# SCHEMATIC_RELAY_DIFFERENTIAL.net
KiCad netlist of a schematic drawn in EasyEDA
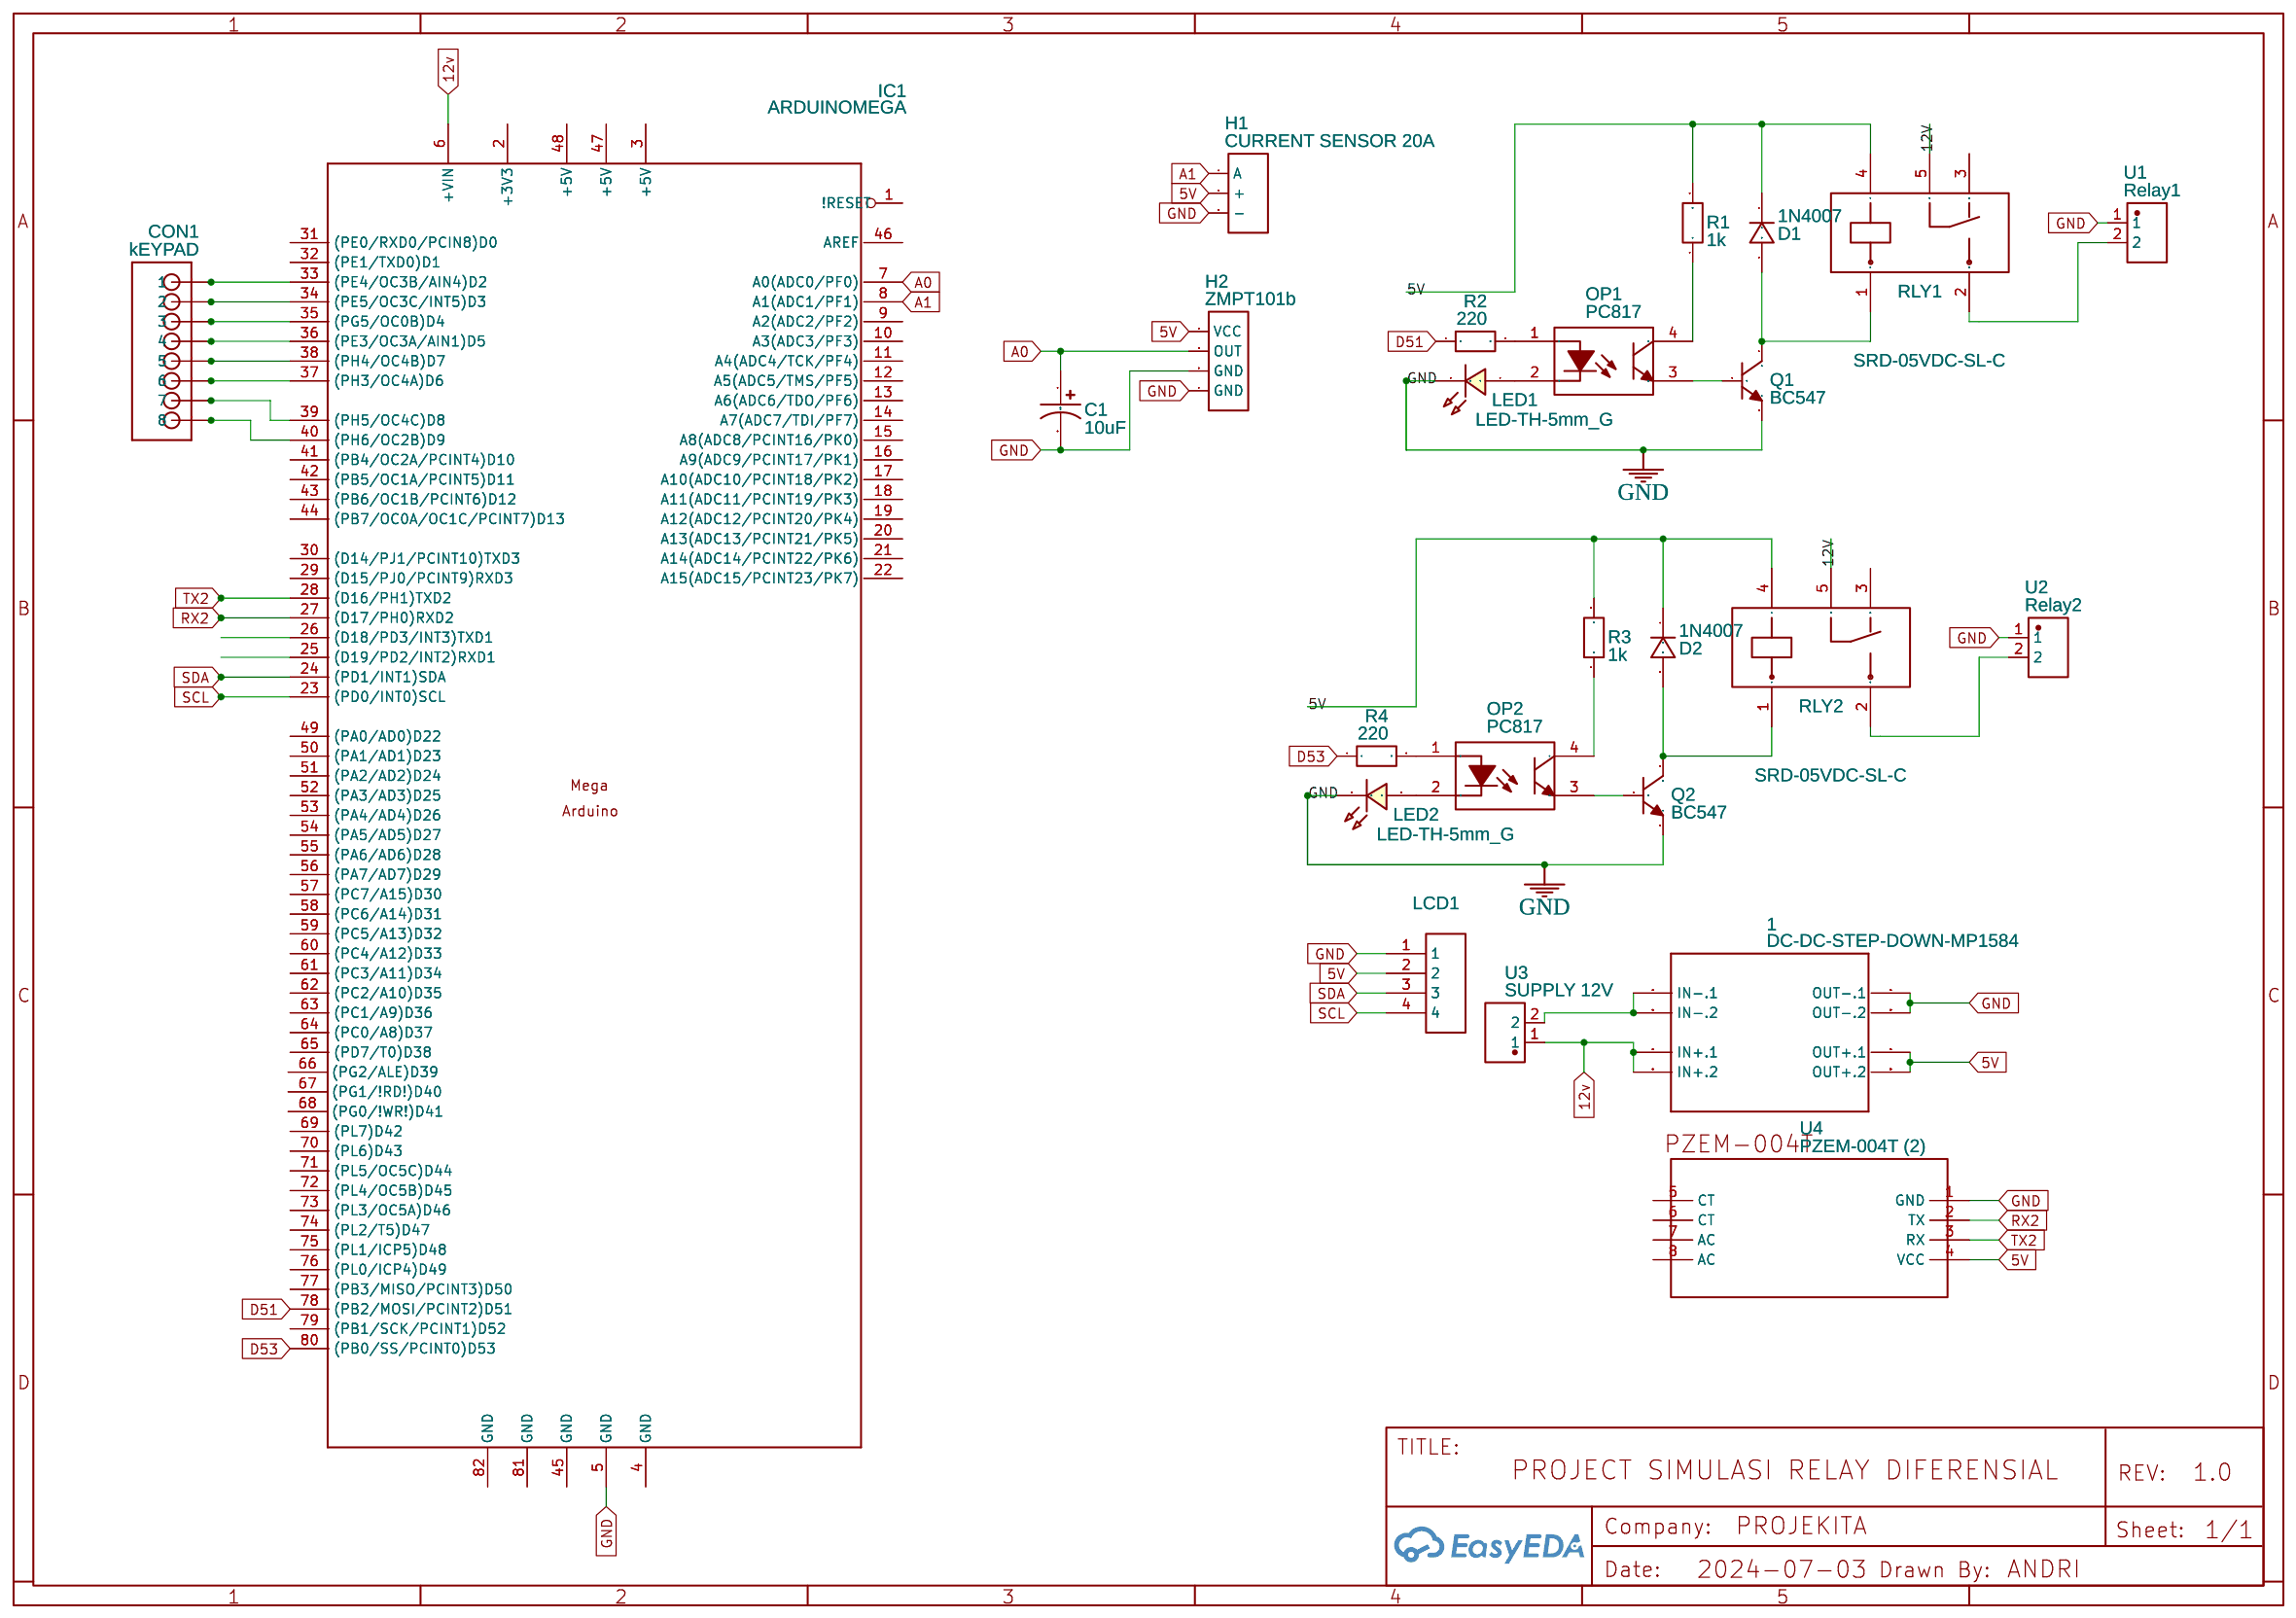
[diagram p0: schematic sheet]

(export (version "E")
  (design (tool "Eeschema 10.0.6"))
  (components
    (comp (ref "1") (value "DC-DC-STEP-DOWN-MP1584") (libsource (lib "") (part "DC-DC-STEP-DOWN-MP1584")))
    (comp (ref "C1") (value "10uF") (libsource (lib "") (part "CE_TH_D4.0×F1.5_US")))
    (comp (ref "CON1") (value "kEYPAD") (libsource (lib "") (part "JST XH2.54 8P")))
    (comp (ref "D1")
      (value "1N4007")
      (fields (field (name "Manufacturer") "SEMTECH"))
      (libsource (lib "") (part "1N4007"))
    )
    (comp (ref "D2")
      (value "1N4007")
      (fields (field (name "Manufacturer") "SEMTECH"))
      (libsource (lib "") (part "1N4007"))
    )
    (comp (ref "H1") (value "CURRENT SENSOR 20A") (libsource (lib "") (part "HDR-F-2.54_1x3")))
    (comp (ref "H2") (value "ZMPT101b") (libsource (lib "") (part "HDR-F-2.54_1x4")))
    (comp (ref "IC1") (value "ARDUINOMEGA") (libsource (lib "") (part "ARDUINOMEGA")))
    (comp (ref "LCD1") (value "NO") (libsource (lib "") (part "JST XH2.54 4 PIN")))
    (comp (ref "LED1")
      (value "LED-TH-5mm_G")
      (fields
        (field (name "Manufacturer Part") "333-2SYGD/S530-E2")
        (field (name "Manufacturer") "EVERLIGHT(台湾亿光)")
      )
      (libsource (lib "") (part "LED-TH-5mm_G"))
    )
    (comp (ref "LED2")
      (value "LED-TH-5mm_G")
      (fields
        (field (name "Manufacturer Part") "333-2SYGD/S530-E2")
        (field (name "Manufacturer") "EVERLIGHT(台湾亿光)")
      )
      (libsource (lib "") (part "LED-TH-5mm_G"))
    )
    (comp (ref "OP1") (value "PC817") (libsource (lib "") (part "PC817")))
    (comp (ref "OP2") (value "PC817") (libsource (lib "") (part "PC817")))
    (comp (ref "Q1")
      (value "BC547")
      (fields (field (name "Manufacturer") "CJ(江苏长电/长晶)"))
      (libsource (lib "") (part "BC547"))
    )
    (comp (ref "Q2")
      (value "BC547")
      (fields (field (name "Manufacturer") "CJ(江苏长电/长晶)"))
      (libsource (lib "") (part "BC547"))
    )
    (comp (ref "R1") (value "1k") (libsource (lib "") (part "R_AXIAL-0.4_EU")))
    (comp (ref "R2") (value "220") (libsource (lib "") (part "R_AXIAL-0.4_EU_1")))
    (comp (ref "R3") (value "1k") (libsource (lib "") (part "R_AXIAL-0.4_EU")))
    (comp (ref "R4") (value "220") (libsource (lib "") (part "R_AXIAL-0.4_EU_1")))
    (comp (ref "RLY1")
      (value "SRD-05VDC-SL-C")
      (fields (field (name "Manufacturer") "松乐"))
      (libsource (lib "") (part "SRD-05VDC-SL-C"))
    )
    (comp (ref "RLY2")
      (value "SRD-05VDC-SL-C")
      (fields (field (name "Manufacturer") "松乐"))
      (libsource (lib "") (part "SRD-05VDC-SL-C"))
    )
    (comp (ref "U1")
      (value "Relay1")
      (fields (field (name "Manufacturer Part") "KF25H-7.62-2P") (field (name "Manufacturer") "KEFA(科发)"))
      (libsource (lib "") (part "KF25H-7.62-2P_1"))
    )
    (comp (ref "U2")
      (value "Relay2")
      (fields (field (name "Manufacturer Part") "KF25H-7.62-2P") (field (name "Manufacturer") "KEFA(科发)"))
      (libsource (lib "") (part "KF25H-7.62-2P_1"))
    )
    (comp (ref "U3")
      (value "SUPPLY 12V")
      (fields (field (name "Manufacturer Part") "KF25H-7.62-2P") (field (name "Manufacturer") "KEFA(科发)"))
      (libsource (lib "") (part "KF25H-7.62-2P"))
    )
    (comp (ref "U4") (value "PZEM-004T (2)") (libsource (lib "") (part "PZEM-004T")))
  )
  (nets
    (net (code "1") (name "/12V") (class "Default")
      (node (ref "RLY1") (pin "5") (pinfunction "5_5") (pintype "input"))
      (node (ref "RLY2") (pin "5") (pinfunction "5_5") (pintype "input"))
    )
    (net (code "2") (name "5V") (class "Default")
      (node (ref "1") (pin "OUT+.1") (pinfunction "OUT+.1_OUT+.1") (pintype "bidirectional"))
      (node (ref "1") (pin "OUT+.2") (pinfunction "OUT+.2_OUT+.2") (pintype "bidirectional"))
      (node (ref "D1") (pin "1") (pinfunction "1_1") (pintype "unspecified"))
      (node (ref "D2") (pin "1") (pinfunction "1_1") (pintype "unspecified"))
      (node (ref "H1") (pin "2") (pinfunction "+_2") (pintype "input"))
      (node (ref "H2") (pin "1") (pinfunction "VCC_1") (pintype "unspecified"))
      (node (ref "LCD1") (pin "2") (pinfunction "2_2") (pintype "unspecified"))
      (node (ref "R1") (pin "2") (pinfunction "2_2") (pintype "unspecified"))
      (node (ref "R3") (pin "2") (pinfunction "2_2") (pintype "unspecified"))
      (node (ref "RLY1") (pin "4") (pinfunction "4_4") (pintype "input"))
      (node (ref "RLY2") (pin "4") (pinfunction "4_4") (pintype "input"))
      (node (ref "U4") (pin "4") (pinfunction "VCC_4") (pintype "unspecified"))
    )
    (net (code "3") (name "12v") (class "Default")
      (node (ref "1") (pin "IN+.1") (pinfunction "IN+.1_IN+.1") (pintype "bidirectional"))
      (node (ref "1") (pin "IN+.2") (pinfunction "IN+.2_IN+.2") (pintype "bidirectional"))
      (node (ref "IC1") (pin "6") (pinfunction "+VIN_6") (pintype "bidirectional"))
      (node (ref "U3") (pin "1") (pinfunction "1_1") (pintype "unspecified"))
    )
    (net (code "4") (name "A0") (class "Default")
      (node (ref "C1") (pin "1") (pinfunction "1_1") (pintype "unspecified"))
      (node (ref "H2") (pin "2") (pinfunction "OUT_2") (pintype "unspecified"))
      (node (ref "IC1") (pin "7") (pinfunction "A0(ADC0/PF0)_7") (pintype "bidirectional"))
    )
    (net (code "5") (name "A1") (class "Default")
      (node (ref "H1") (pin "1") (pinfunction "A_1") (pintype "input"))
      (node (ref "IC1") (pin "8") (pinfunction "A1(ADC1/PF1)_8") (pintype "bidirectional"))
    )
    (net (code "6") (name "D51") (class "Default")
      (node (ref "IC1") (pin "78") (pinfunction "(PB2/MOSI/PCINT2)D51_78") (pintype "bidirectional"))
      (node (ref "R2") (pin "1") (pinfunction "1_1") (pintype "unspecified"))
    )
    (net (code "7") (name "D53") (class "Default")
      (node (ref "IC1") (pin "80") (pinfunction "(PB0/SS/PCINT0)D53_80") (pintype "bidirectional"))
      (node (ref "R4") (pin "1") (pinfunction "1_1") (pintype "unspecified"))
    )
    (net (code "8") (name "GND") (class "Default")
      (node (ref "1") (pin "OUT-.1") (pinfunction "OUT-.1_OUT-.1") (pintype "bidirectional"))
      (node (ref "1") (pin "OUT-.2") (pinfunction "OUT-.2_OUT-.2") (pintype "bidirectional"))
      (node (ref "C1") (pin "2") (pinfunction "2_2") (pintype "unspecified"))
      (node (ref "H1") (pin "3") (pinfunction "-_3") (pintype "input"))
      (node (ref "H2") (pin "3") (pinfunction "GND_3") (pintype "unspecified"))
      (node (ref "H2") (pin "4") (pinfunction "GND_4") (pintype "unspecified"))
      (node (ref "IC1") (pin "5") (pinfunction "GND_5") (pintype "bidirectional"))
      (node (ref "LCD1") (pin "1") (pinfunction "1_1") (pintype "unspecified"))
      (node (ref "LED1") (pin "2") (pinfunction "2_2") (pintype "unspecified"))
      (node (ref "LED2") (pin "2") (pinfunction "2_2") (pintype "unspecified"))
      (node (ref "Q1") (pin "3") (pinfunction "E_3") (pintype "unspecified"))
      (node (ref "Q2") (pin "3") (pinfunction "E_3") (pintype "unspecified"))
      (node (ref "U1") (pin "1") (pinfunction "1_1") (pintype "unspecified"))
      (node (ref "U2") (pin "1") (pinfunction "1_1") (pintype "unspecified"))
      (node (ref "U4") (pin "1") (pinfunction "GND_1") (pintype "unspecified"))
    )
    (net (code "9") (name "Net-(1-PadIN-.1)") (class "Default")
      (node (ref "1") (pin "IN-.1") (pinfunction "IN-.1_IN-.1") (pintype "bidirectional"))
      (node (ref "1") (pin "IN-.2") (pinfunction "IN-.2_IN-.2") (pintype "bidirectional"))
      (node (ref "U3") (pin "2") (pinfunction "2_2") (pintype "unspecified"))
    )
    (net (code "10") (name "Net-(IC1-(PE3{slash}OC3A{slash}AIN1)D5)") (class "Default")
      (node (ref "CON1") (pin "4") (pinfunction "4_4") (pintype "unspecified"))
      (node (ref "IC1") (pin "36") (pinfunction "(PE3/OC3A/AIN1)D5_36") (pintype "bidirectional"))
    )
    (net (code "11") (name "Net-(IC1-(PE4{slash}OC3B{slash}AIN4)D2)") (class "Default")
      (node (ref "CON1") (pin "1") (pinfunction "1_1") (pintype "unspecified"))
      (node (ref "IC1") (pin "33") (pinfunction "(PE4/OC3B/AIN4)D2_33") (pintype "bidirectional"))
    )
    (net (code "12") (name "Net-(IC1-(PE5{slash}OC3C{slash}INT5)D3)") (class "Default")
      (node (ref "CON1") (pin "2") (pinfunction "2_2") (pintype "unspecified"))
      (node (ref "IC1") (pin "34") (pinfunction "(PE5/OC3C/INT5)D3_34") (pintype "bidirectional"))
    )
    (net (code "13") (name "Net-(IC1-(PG5{slash}OC0B)D4)") (class "Default")
      (node (ref "CON1") (pin "3") (pinfunction "3_3") (pintype "unspecified"))
      (node (ref "IC1") (pin "35") (pinfunction "(PG5/OC0B)D4_35") (pintype "bidirectional"))
    )
    (net (code "14") (name "Net-(IC1-(PH3{slash}OC4A)D6)") (class "Default")
      (node (ref "CON1") (pin "6") (pinfunction "6_6") (pintype "unspecified"))
      (node (ref "IC1") (pin "37") (pinfunction "(PH3/OC4A)D6_37") (pintype "bidirectional"))
    )
    (net (code "15") (name "Net-(IC1-(PH4{slash}OC4B)D7)") (class "Default")
      (node (ref "CON1") (pin "5") (pinfunction "5_5") (pintype "unspecified"))
      (node (ref "IC1") (pin "38") (pinfunction "(PH4/OC4B)D7_38") (pintype "bidirectional"))
    )
    (net (code "16") (name "Net-(IC1-(PH5{slash}OC4C)D8)") (class "Default")
      (node (ref "CON1") (pin "7") (pinfunction "7_7") (pintype "unspecified"))
      (node (ref "IC1") (pin "39") (pinfunction "(PH5/OC4C)D8_39") (pintype "bidirectional"))
    )
    (net (code "17") (name "Net-(IC1-(PH6{slash}OC2B)D9)") (class "Default")
      (node (ref "CON1") (pin "8") (pinfunction "8_8") (pintype "unspecified"))
      (node (ref "IC1") (pin "40") (pinfunction "(PH6/OC2B)D9_40") (pintype "bidirectional"))
    )
    (net (code "18") (name "Net-(LED1-Pad1)") (class "Default")
      (node (ref "LED1") (pin "1") (pinfunction "1_1") (pintype "unspecified"))
      (node (ref "OP1") (pin "2") (pinfunction "2_2") (pintype "unspecified"))
    )
    (net (code "19") (name "Net-(LED2-Pad1)") (class "Default")
      (node (ref "LED2") (pin "1") (pinfunction "1_1") (pintype "unspecified"))
      (node (ref "OP2") (pin "2") (pinfunction "2_2") (pintype "unspecified"))
    )
    (net (code "20") (name "Net-(OP1-Pad1)") (class "Default")
      (node (ref "OP1") (pin "1") (pinfunction "1_1") (pintype "unspecified"))
      (node (ref "R2") (pin "2") (pinfunction "2_2") (pintype "unspecified"))
    )
    (net (code "21") (name "Net-(OP1-Pad4)") (class "Default")
      (node (ref "OP1") (pin "4") (pinfunction "4_4") (pintype "unspecified"))
      (node (ref "R1") (pin "1") (pinfunction "1_1") (pintype "unspecified"))
    )
    (net (code "22") (name "Net-(OP2-Pad1)") (class "Default")
      (node (ref "OP2") (pin "1") (pinfunction "1_1") (pintype "unspecified"))
      (node (ref "R4") (pin "2") (pinfunction "2_2") (pintype "unspecified"))
    )
    (net (code "23") (name "Net-(OP2-Pad4)") (class "Default")
      (node (ref "OP2") (pin "4") (pinfunction "4_4") (pintype "unspecified"))
      (node (ref "R3") (pin "1") (pinfunction "1_1") (pintype "unspecified"))
    )
    (net (code "24") (name "Net-(Q1-B)") (class "Default")
      (node (ref "OP1") (pin "3") (pinfunction "3_3") (pintype "unspecified"))
      (node (ref "Q1") (pin "2") (pinfunction "B_2") (pintype "unspecified"))
    )
    (net (code "25") (name "Net-(Q1-C)") (class "Default")
      (node (ref "D1") (pin "2") (pinfunction "2_2") (pintype "unspecified"))
      (node (ref "Q1") (pin "1") (pinfunction "C_1") (pintype "unspecified"))
      (node (ref "RLY1") (pin "1") (pinfunction "1_1") (pintype "input"))
    )
    (net (code "26") (name "Net-(Q2-B)") (class "Default")
      (node (ref "OP2") (pin "3") (pinfunction "3_3") (pintype "unspecified"))
      (node (ref "Q2") (pin "2") (pinfunction "B_2") (pintype "unspecified"))
    )
    (net (code "27") (name "Net-(Q2-C)") (class "Default")
      (node (ref "D2") (pin "2") (pinfunction "2_2") (pintype "unspecified"))
      (node (ref "Q2") (pin "1") (pinfunction "C_1") (pintype "unspecified"))
      (node (ref "RLY2") (pin "1") (pinfunction "1_1") (pintype "input"))
    )
    (net (code "28") (name "Net-(RLY1-Pad2)") (class "Default")
      (node (ref "RLY1") (pin "2") (pinfunction "2_2") (pintype "input"))
      (node (ref "U1") (pin "2") (pinfunction "2_2") (pintype "unspecified"))
    )
    (net (code "29") (name "Net-(RLY2-Pad2)") (class "Default")
      (node (ref "RLY2") (pin "2") (pinfunction "2_2") (pintype "input"))
      (node (ref "U2") (pin "2") (pinfunction "2_2") (pintype "unspecified"))
    )
    (net (code "30") (name "RX2") (class "Default")
      (node (ref "IC1") (pin "27") (pinfunction "(D17/PH0)RXD2_27") (pintype "bidirectional"))
      (node (ref "U4") (pin "2") (pinfunction "TX_2") (pintype "unspecified"))
    )
    (net (code "31") (name "SCL") (class "Default")
      (node (ref "IC1") (pin "23") (pinfunction "(PD0/INT0)SCL_23") (pintype "bidirectional"))
      (node (ref "LCD1") (pin "4") (pinfunction "4_4") (pintype "unspecified"))
    )
    (net (code "32") (name "SDA") (class "Default")
      (node (ref "IC1") (pin "24") (pinfunction "(PD1/INT1)SDA_24") (pintype "bidirectional"))
      (node (ref "LCD1") (pin "3") (pinfunction "3_3") (pintype "unspecified"))
    )
    (net (code "33") (name "TX2") (class "Default")
      (node (ref "IC1") (pin "28") (pinfunction "(D16/PH1)TXD2_28") (pintype "bidirectional"))
      (node (ref "U4") (pin "3") (pinfunction "RX_3") (pintype "unspecified"))
    )
    (net (code "34") (name "unconnected-(IC1-!RESET-Pad1)") (class "Default")
      (node (ref "IC1") (pin "1") (pinfunction "!RESET_1") (pintype "bidirectional"))
    )
    (net (code "35") (name "unconnected-(IC1-(D14{slash}PJ1{slash}PCINT10)TXD3-Pad30)") (class "Default")
      (node (ref "IC1") (pin "30") (pinfunction "(D14/PJ1/PCINT10)TXD3_30") (pintype "bidirectional"))
    )
    (net (code "36") (name "unconnected-(IC1-(D15{slash}PJ0{slash}PCINT9)RXD3-Pad29)") (class "Default")
      (node (ref "IC1") (pin "29") (pinfunction "(D15/PJ0/PCINT9)RXD3_29") (pintype "bidirectional"))
    )
    (net (code "37") (name "unconnected-(IC1-(D18{slash}PD3{slash}INT3)TXD1-Pad26)") (class "Default")
      (node (ref "IC1") (pin "26") (pinfunction "(D18/PD3/INT3)TXD1_26") (pintype "bidirectional"))
    )
    (net (code "38") (name "unconnected-(IC1-(D19{slash}PD2{slash}INT2)RXD1-Pad25)") (class "Default")
      (node (ref "IC1") (pin "25") (pinfunction "(D19/PD2/INT2)RXD1_25") (pintype "bidirectional"))
    )
    (net (code "39") (name "unconnected-(IC1-(PA0{slash}AD0)D22-Pad49)") (class "Default")
      (node (ref "IC1") (pin "49") (pinfunction "(PA0/AD0)D22_49") (pintype "bidirectional"))
    )
    (net (code "40") (name "unconnected-(IC1-(PA1{slash}AD1)D23-Pad50)") (class "Default")
      (node (ref "IC1") (pin "50") (pinfunction "(PA1/AD1)D23_50") (pintype "bidirectional"))
    )
    (net (code "41") (name "unconnected-(IC1-(PA2{slash}AD2)D24-Pad51)") (class "Default")
      (node (ref "IC1") (pin "51") (pinfunction "(PA2/AD2)D24_51") (pintype "bidirectional"))
    )
    (net (code "42") (name "unconnected-(IC1-(PA3{slash}AD3)D25-Pad52)") (class "Default")
      (node (ref "IC1") (pin "52") (pinfunction "(PA3/AD3)D25_52") (pintype "bidirectional"))
    )
    (net (code "43") (name "unconnected-(IC1-(PA4{slash}AD4)D26-Pad53)") (class "Default")
      (node (ref "IC1") (pin "53") (pinfunction "(PA4/AD4)D26_53") (pintype "bidirectional"))
    )
    (net (code "44") (name "unconnected-(IC1-(PA5{slash}AD5)D27-Pad54)") (class "Default")
      (node (ref "IC1") (pin "54") (pinfunction "(PA5/AD5)D27_54") (pintype "bidirectional"))
    )
    (net (code "45") (name "unconnected-(IC1-(PA6{slash}AD6)D28-Pad55)") (class "Default")
      (node (ref "IC1") (pin "55") (pinfunction "(PA6/AD6)D28_55") (pintype "bidirectional"))
    )
    (net (code "46") (name "unconnected-(IC1-(PA7{slash}AD7)D29-Pad56)") (class "Default")
      (node (ref "IC1") (pin "56") (pinfunction "(PA7/AD7)D29_56") (pintype "bidirectional"))
    )
    (net (code "47") (name "unconnected-(IC1-(PB1{slash}SCK{slash}PCINT1)D52-Pad79)") (class "Default")
      (node (ref "IC1") (pin "79") (pinfunction "(PB1/SCK/PCINT1)D52_79") (pintype "bidirectional"))
    )
    (net (code "48") (name "unconnected-(IC1-(PB3{slash}MISO{slash}PCINT3)D50-Pad77)") (class "Default")
      (node (ref "IC1") (pin "77") (pinfunction "(PB3/MISO/PCINT3)D50_77") (pintype "bidirectional"))
    )
    (net (code "49") (name "unconnected-(IC1-(PB4{slash}OC2A{slash}PCINT4)D10-Pad41)") (class "Default")
      (node (ref "IC1") (pin "41") (pinfunction "(PB4/OC2A/PCINT4)D10_41") (pintype "bidirectional"))
    )
    (net (code "50") (name "unconnected-(IC1-(PB5{slash}OC1A{slash}PCINT5)D11-Pad42)") (class "Default")
      (node (ref "IC1") (pin "42") (pinfunction "(PB5/OC1A/PCINT5)D11_42") (pintype "bidirectional"))
    )
    (net (code "51") (name "unconnected-(IC1-(PB6{slash}OC1B{slash}PCINT6)D12-Pad43)") (class "Default")
      (node (ref "IC1") (pin "43") (pinfunction "(PB6/OC1B/PCINT6)D12_43") (pintype "bidirectional"))
    )
    (net (code "52") (name "unconnected-(IC1-(PB7{slash}OC0A{slash}OC1C{slash}PCINT7)D13-Pad44)") (class "Default")
      (node (ref "IC1") (pin "44") (pinfunction "(PB7/OC0A/OC1C/PCINT7)D13_44") (pintype "bidirectional"))
    )
    (net (code "53") (name "unconnected-(IC1-(PC0{slash}A8)D37-Pad64)") (class "Default")
      (node (ref "IC1") (pin "64") (pinfunction "(PC0/A8)D37_64") (pintype "bidirectional"))
    )
    (net (code "54") (name "unconnected-(IC1-(PC1{slash}A9)D36-Pad63)") (class "Default")
      (node (ref "IC1") (pin "63") (pinfunction "(PC1/A9)D36_63") (pintype "bidirectional"))
    )
    (net (code "55") (name "unconnected-(IC1-(PC2{slash}A10)D35-Pad62)") (class "Default")
      (node (ref "IC1") (pin "62") (pinfunction "(PC2/A10)D35_62") (pintype "bidirectional"))
    )
    (net (code "56") (name "unconnected-(IC1-(PC3{slash}A11)D34-Pad61)") (class "Default")
      (node (ref "IC1") (pin "61") (pinfunction "(PC3/A11)D34_61") (pintype "bidirectional"))
    )
    (net (code "57") (name "unconnected-(IC1-(PC4{slash}A12)D33-Pad60)") (class "Default")
      (node (ref "IC1") (pin "60") (pinfunction "(PC4/A12)D33_60") (pintype "bidirectional"))
    )
    (net (code "58") (name "unconnected-(IC1-(PC5{slash}A13)D32-Pad59)") (class "Default")
      (node (ref "IC1") (pin "59") (pinfunction "(PC5/A13)D32_59") (pintype "bidirectional"))
    )
    (net (code "59") (name "unconnected-(IC1-(PC6{slash}A14)D31-Pad58)") (class "Default")
      (node (ref "IC1") (pin "58") (pinfunction "(PC6/A14)D31_58") (pintype "bidirectional"))
    )
    (net (code "60") (name "unconnected-(IC1-(PC7{slash}A15)D30-Pad57)") (class "Default")
      (node (ref "IC1") (pin "57") (pinfunction "(PC7/A15)D30_57") (pintype "bidirectional"))
    )
    (net (code "61") (name "unconnected-(IC1-(PD7{slash}T0)D38-Pad65)") (class "Default")
      (node (ref "IC1") (pin "65") (pinfunction "(PD7/T0)D38_65") (pintype "bidirectional"))
    )
    (net (code "62") (name "unconnected-(IC1-(PE0{slash}RXD0{slash}PCIN8)D0-Pad31)") (class "Default")
      (node (ref "IC1") (pin "31") (pinfunction "(PE0/RXD0/PCIN8)D0_31") (pintype "bidirectional"))
    )
    (net (code "63") (name "unconnected-(IC1-(PE1{slash}TXD0)D1-Pad32)") (class "Default")
      (node (ref "IC1") (pin "32") (pinfunction "(PE1/TXD0)D1_32") (pintype "bidirectional"))
    )
    (net (code "64") (name "unconnected-(IC1-(PG0{slash}!WR!)D41-Pad68)") (class "Default")
      (node (ref "IC1") (pin "68") (pinfunction "(PG0/!WR!)D41_68") (pintype "bidirectional"))
    )
    (net (code "65") (name "unconnected-(IC1-(PG1{slash}!RD!)D40-Pad67)") (class "Default")
      (node (ref "IC1") (pin "67") (pinfunction "(PG1/!RD!)D40_67") (pintype "bidirectional"))
    )
    (net (code "66") (name "unconnected-(IC1-(PG2{slash}ALE)D39-Pad66)") (class "Default")
      (node (ref "IC1") (pin "66") (pinfunction "(PG2/ALE)D39_66") (pintype "bidirectional"))
    )
    (net (code "67") (name "unconnected-(IC1-(PL0{slash}ICP4)D49-Pad76)") (class "Default")
      (node (ref "IC1") (pin "76") (pinfunction "(PL0/ICP4)D49_76") (pintype "bidirectional"))
    )
    (net (code "68") (name "unconnected-(IC1-(PL1{slash}ICP5)D48-Pad75)") (class "Default")
      (node (ref "IC1") (pin "75") (pinfunction "(PL1/ICP5)D48_75") (pintype "bidirectional"))
    )
    (net (code "69") (name "unconnected-(IC1-(PL2{slash}T5)D47-Pad74)") (class "Default")
      (node (ref "IC1") (pin "74") (pinfunction "(PL2/T5)D47_74") (pintype "bidirectional"))
    )
    (net (code "70") (name "unconnected-(IC1-(PL3{slash}OC5A)D46-Pad73)") (class "Default")
      (node (ref "IC1") (pin "73") (pinfunction "(PL3/OC5A)D46_73") (pintype "bidirectional"))
    )
    (net (code "71") (name "unconnected-(IC1-(PL4{slash}OC5B)D45-Pad72)") (class "Default")
      (node (ref "IC1") (pin "72") (pinfunction "(PL4/OC5B)D45_72") (pintype "bidirectional"))
    )
    (net (code "72") (name "unconnected-(IC1-(PL5{slash}OC5C)D44-Pad71)") (class "Default")
      (node (ref "IC1") (pin "71") (pinfunction "(PL5/OC5C)D44_71") (pintype "bidirectional"))
    )
    (net (code "73") (name "unconnected-(IC1-(PL6)D43-Pad70)") (class "Default")
      (node (ref "IC1") (pin "70") (pinfunction "(PL6)D43_70") (pintype "bidirectional"))
    )
    (net (code "74") (name "unconnected-(IC1-(PL7)D42-Pad69)") (class "Default")
      (node (ref "IC1") (pin "69") (pinfunction "(PL7)D42_69") (pintype "bidirectional"))
    )
    (net (code "75") (name "unconnected-(IC1-+3V3-Pad2)") (class "Default")
      (node (ref "IC1") (pin "2") (pinfunction "+3V3_2") (pintype "bidirectional"))
    )
    (net (code "76") (name "unconnected-(IC1-+5V-Pad3)") (class "Default")
      (node (ref "IC1") (pin "3") (pinfunction "+5V_3") (pintype "bidirectional"))
    )
    (net (code "77") (name "unconnected-(IC1-+5V-Pad47)") (class "Default")
      (node (ref "IC1") (pin "47") (pinfunction "+5V_47") (pintype "bidirectional"))
    )
    (net (code "78") (name "unconnected-(IC1-+5V-Pad48)") (class "Default")
      (node (ref "IC1") (pin "48") (pinfunction "+5V_48") (pintype "bidirectional"))
    )
    (net (code "79") (name "unconnected-(IC1-A2(ADC2{slash}PF2)-Pad9)") (class "Default")
      (node (ref "IC1") (pin "9") (pinfunction "A2(ADC2/PF2)_9") (pintype "bidirectional"))
    )
    (net (code "80") (name "unconnected-(IC1-A3(ADC3{slash}PF3)-Pad10)") (class "Default")
      (node (ref "IC1") (pin "10") (pinfunction "A3(ADC3/PF3)_10") (pintype "bidirectional"))
    )
    (net (code "81") (name "unconnected-(IC1-A4(ADC4{slash}TCK{slash}PF4)-Pad11)") (class "Default")
      (node (ref "IC1") (pin "11") (pinfunction "A4(ADC4/TCK/PF4)_11") (pintype "bidirectional"))
    )
    (net (code "82") (name "unconnected-(IC1-A5(ADC5{slash}TMS{slash}PF5)-Pad12)") (class "Default")
      (node (ref "IC1") (pin "12") (pinfunction "A5(ADC5/TMS/PF5)_12") (pintype "bidirectional"))
    )
    (net (code "83") (name "unconnected-(IC1-A6(ADC6{slash}TDO{slash}PF6)-Pad13)") (class "Default")
      (node (ref "IC1") (pin "13") (pinfunction "A6(ADC6/TDO/PF6)_13") (pintype "bidirectional"))
    )
    (net (code "84") (name "unconnected-(IC1-A7(ADC7{slash}TDI{slash}PF7)-Pad14)") (class "Default")
      (node (ref "IC1") (pin "14") (pinfunction "A7(ADC7/TDI/PF7)_14") (pintype "bidirectional"))
    )
    (net (code "85") (name "unconnected-(IC1-A8(ADC8{slash}PCINT16{slash}PK0)-Pad15)") (class "Default")
      (node (ref "IC1") (pin "15") (pinfunction "A8(ADC8/PCINT16/PK0)_15") (pintype "bidirectional"))
    )
    (net (code "86") (name "unconnected-(IC1-A9(ADC9{slash}PCINT17{slash}PK1)-Pad16)") (class "Default")
      (node (ref "IC1") (pin "16") (pinfunction "A9(ADC9/PCINT17/PK1)_16") (pintype "bidirectional"))
    )
    (net (code "87") (name "unconnected-(IC1-A10(ADC10{slash}PCINT18{slash}PK2)-Pad17)") (class "Default")
      (node (ref "IC1") (pin "17") (pinfunction "A10(ADC10/PCINT18/PK2)_17") (pintype "bidirectional"))
    )
    (net (code "88") (name "unconnected-(IC1-A11(ADC11{slash}PCINT19{slash}PK3)-Pad18)") (class "Default")
      (node (ref "IC1") (pin "18") (pinfunction "A11(ADC11/PCINT19/PK3)_18") (pintype "bidirectional"))
    )
    (net (code "89") (name "unconnected-(IC1-A12(ADC12{slash}PCINT20{slash}PK4)-Pad19)") (class "Default")
      (node (ref "IC1") (pin "19") (pinfunction "A12(ADC12/PCINT20/PK4)_19") (pintype "bidirectional"))
    )
    (net (code "90") (name "unconnected-(IC1-A13(ADC13{slash}PCINT21{slash}PK5)-Pad20)") (class "Default")
      (node (ref "IC1") (pin "20") (pinfunction "A13(ADC13/PCINT21/PK5)_20") (pintype "bidirectional"))
    )
    (net (code "91") (name "unconnected-(IC1-A14(ADC14{slash}PCINT22{slash}PK6)-Pad21)") (class "Default")
      (node (ref "IC1") (pin "21") (pinfunction "A14(ADC14/PCINT22/PK6)_21") (pintype "bidirectional"))
    )
    (net (code "92") (name "unconnected-(IC1-A15(ADC15{slash}PCINT23{slash}PK7)-Pad22)") (class "Default")
      (node (ref "IC1") (pin "22") (pinfunction "A15(ADC15/PCINT23/PK7)_22") (pintype "bidirectional"))
    )
    (net (code "93") (name "unconnected-(IC1-AREF-Pad46)") (class "Default")
      (node (ref "IC1") (pin "46") (pinfunction "AREF_46") (pintype "bidirectional"))
    )
    (net (code "94") (name "unconnected-(IC1-GND-Pad4)") (class "Default")
      (node (ref "IC1") (pin "4") (pinfunction "GND_4") (pintype "bidirectional"))
    )
    (net (code "95") (name "unconnected-(IC1-GND-Pad45)") (class "Default")
      (node (ref "IC1") (pin "45") (pinfunction "GND_45") (pintype "bidirectional"))
    )
    (net (code "96") (name "unconnected-(IC1-GND-Pad81)") (class "Default")
      (node (ref "IC1") (pin "81") (pinfunction "GND_81") (pintype "bidirectional"))
    )
    (net (code "97") (name "unconnected-(IC1-GND-Pad82)") (class "Default")
      (node (ref "IC1") (pin "82") (pinfunction "GND_82") (pintype "bidirectional"))
    )
    (net (code "98") (name "unconnected-(RLY1-Pad3)") (class "Default")
      (node (ref "RLY1") (pin "3") (pinfunction "3_3") (pintype "input"))
    )
    (net (code "99") (name "unconnected-(RLY2-Pad3)") (class "Default")
      (node (ref "RLY2") (pin "3") (pinfunction "3_3") (pintype "input"))
    )
    (net (code "100") (name "unconnected-(U4-AC-Pad7)") (class "Default")
      (node (ref "U4") (pin "7") (pinfunction "AC_7") (pintype "unspecified"))
    )
    (net (code "101") (name "unconnected-(U4-AC-Pad8)") (class "Default")
      (node (ref "U4") (pin "8") (pinfunction "AC_8") (pintype "unspecified"))
    )
    (net (code "102") (name "unconnected-(U4-CT-Pad5)") (class "Default")
      (node (ref "U4") (pin "5") (pinfunction "CT_5") (pintype "unspecified"))
    )
    (net (code "103") (name "unconnected-(U4-CT-Pad6)") (class "Default")
      (node (ref "U4") (pin "6") (pinfunction "CT_6") (pintype "unspecified"))
    )
  )
)
